# fuelboxmp3.net
KiCad netlist of a schematic drawn in EAGLE
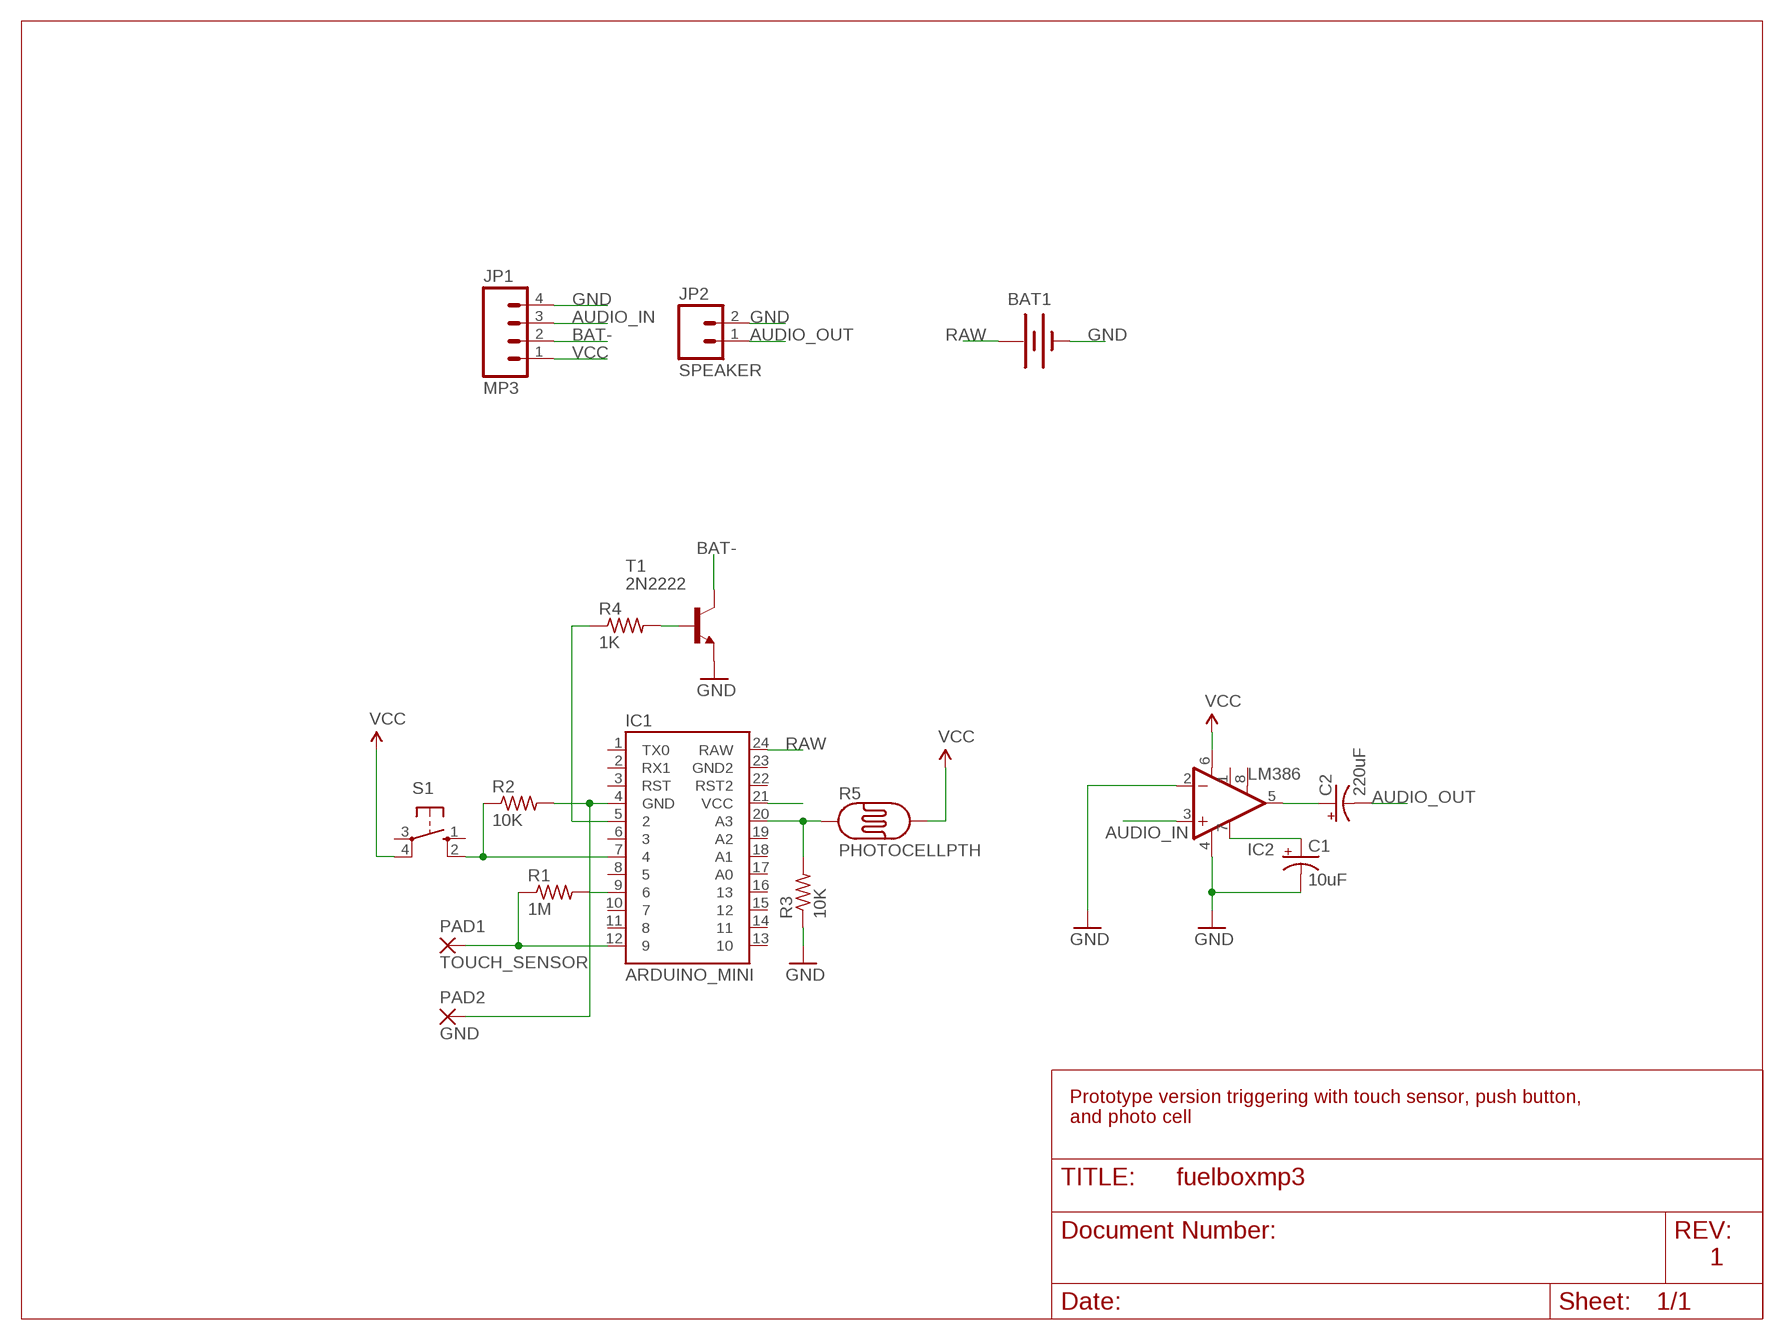
[diagram p0: schematic, sheet 1]

(export (version "E")
  (design (tool "Eeschema 10.0.6"))
  (components
    (comp (ref "BAT1")
      (value "BATTERY1100")
      (footprint "eagle-import:LIPO-1100MAH")
      (libsource (lib "eagle-import") (part "BATTERY1100"))
    )
    (comp (ref "C1")
      (value "10uF")
      (footprint "eagle-import:E2,5-5")
      (libsource (lib "eagle-import") (part "CPOL-USE2.5-5"))
    )
    (comp (ref "C2")
      (value "220uF")
      (footprint "eagle-import:E2,5-6")
      (libsource (lib "eagle-import") (part "CPOL-USE2.5-6"))
    )
    (comp (ref "IC1")
      (value "ARDUINO_MINI")
      (footprint "eagle-import:ARDUINO_MINI")
      (libsource (lib "eagle-import") (part "ARDUINO_MINI"))
    )
    (comp (ref "IC2")
      (value "LM386")
      (footprint "eagle-import:DIP08")
      (libsource (lib "eagle-import") (part "LM386"))
    )
    (comp (ref "JP1")
      (value "MP3")
      (footprint "eagle-import:1X04")
      (libsource (lib "eagle-import") (part "M04PTH"))
    )
    (comp (ref "JP2")
      (value "SPEAKER")
      (footprint "eagle-import:1X02")
      (libsource (lib "eagle-import") (part "M02PTH"))
    )
    (comp (ref "PAD1")
      (value "TOUCH_SENSOR")
      (footprint "eagle-import:3,81_1,1")
      (libsource (lib "eagle-import") (part "WIREPAD3,81/1,1"))
    )
    (comp (ref "PAD2")
      (value "GND")
      (footprint "eagle-import:3,81_1,1")
      (libsource (lib "eagle-import") (part "WIREPAD3,81/1,1"))
    )
    (comp (ref "R1")
      (value "1M")
      (footprint "eagle-import:0204_7")
      (libsource (lib "eagle-import") (part "R-US_0204/7"))
    )
    (comp (ref "R2")
      (value "10K")
      (footprint "eagle-import:0204_7")
      (libsource (lib "eagle-import") (part "R-US_0204/7"))
    )
    (comp (ref "R3")
      (value "10K")
      (footprint "eagle-import:0204_7")
      (libsource (lib "eagle-import") (part "R-US_0204/7"))
    )
    (comp (ref "R4")
      (value "1K")
      (footprint "eagle-import:0204_7")
      (libsource (lib "eagle-import") (part "R-US_0204/7"))
    )
    (comp (ref "R5")
      (value "PHOTOCELLPTH")
      (footprint "eagle-import:PHOTOCELL")
      (libsource (lib "eagle-import") (part "PHOTOCELLPTH"))
    )
    (comp (ref "S1")
      (value "10-XX")
      (footprint "eagle-import:B3F-10XX")
      (fields (field (name "MPN") "B3F-1000"))
      (libsource (lib "eagle-import") (part "10-XX"))
    )
    (comp (ref "T1")
      (value "2N2222")
      (footprint "eagle-import:TO92-EBC-OVAL")
      (libsource (lib "eagle-import") (part "2N2222"))
    )
  )
  (nets
    (net (code "1") (name "/AUDIO_IN") (class "Default")
      (node (ref "IC2") (pin "3") (pinfunction "+IN_3") (pintype "input"))
      (node (ref "JP1") (pin "3") (pinfunction "3_3") (pintype "passive"))
    )
    (net (code "2") (name "/AUDIO_OUT") (class "Default")
      (node (ref "C2") (pin "-") (pinfunction "-_-") (pintype "passive"))
      (node (ref "JP2") (pin "1") (pinfunction "1_1") (pintype "passive"))
    )
    (net (code "3") (name "/BAT-") (class "Default")
      (node (ref "JP1") (pin "2") (pinfunction "2_2") (pintype "passive"))
      (node (ref "T1") (pin "C") (pinfunction "C_C") (pintype "passive"))
    )
    (net (code "4") (name "/RAW") (class "Default")
      (node (ref "BAT1") (pin "+") (pinfunction "+_+") (pintype "power_in"))
      (node (ref "IC1") (pin "24") (pinfunction "RAW_24") (pintype "bidirectional"))
    )
    (net (code "5") (name "GND") (class "Default")
      (node (ref "BAT1") (pin "-") (pinfunction "-_-") (pintype "power_in"))
      (node (ref "C1") (pin "-") (pinfunction "-_-") (pintype "passive"))
      (node (ref "IC1") (pin "4") (pinfunction "GND_4") (pintype "bidirectional"))
      (node (ref "IC2") (pin "2") (pinfunction "-IN_2") (pintype "input"))
      (node (ref "IC2") (pin "4") (pinfunction "V-_4") (pintype "power_in"))
      (node (ref "JP1") (pin "4") (pinfunction "4_4") (pintype "passive"))
      (node (ref "JP2") (pin "2") (pinfunction "2_2") (pintype "passive"))
      (node (ref "PAD2") (pin "1") (pinfunction "P_1") (pintype "passive"))
      (node (ref "R2") (pin "2") (pinfunction "2_2") (pintype "passive"))
      (node (ref "R3") (pin "1") (pinfunction "1_1") (pintype "passive"))
      (node (ref "T1") (pin "E") (pinfunction "E_E") (pintype "passive"))
    )
    (net (code "6") (name "Net-(IC1-2)") (class "Default")
      (node (ref "IC1") (pin "5") (pinfunction "2_5") (pintype "bidirectional"))
      (node (ref "R4") (pin "1") (pinfunction "1_1") (pintype "passive"))
    )
    (net (code "7") (name "Net-(IC1-4)") (class "Default")
      (node (ref "IC1") (pin "7") (pinfunction "4_7") (pintype "bidirectional"))
      (node (ref "R2") (pin "1") (pinfunction "1_1") (pintype "passive"))
      (node (ref "S1") (pin "2") (pinfunction "S1_2") (pintype "passive"))
    )
    (net (code "8") (name "Net-(IC1-6)") (class "Default")
      (node (ref "IC1") (pin "9") (pinfunction "6_9") (pintype "bidirectional"))
      (node (ref "R1") (pin "2") (pinfunction "2_2") (pintype "passive"))
    )
    (net (code "9") (name "Net-(IC1-9)") (class "Default")
      (node (ref "IC1") (pin "12") (pinfunction "9_12") (pintype "bidirectional"))
      (node (ref "PAD1") (pin "1") (pinfunction "P_1") (pintype "passive"))
      (node (ref "R1") (pin "1") (pinfunction "1_1") (pintype "passive"))
    )
    (net (code "10") (name "Net-(IC1-A3)") (class "Default")
      (node (ref "IC1") (pin "20") (pinfunction "A3_20") (pintype "bidirectional"))
      (node (ref "R3") (pin "2") (pinfunction "2_2") (pintype "passive"))
      (node (ref "R5") (pin "1") (pinfunction "P$1_1") (pintype "bidirectional"))
    )
    (net (code "11") (name "Net-(IC2-BP)") (class "Default")
      (node (ref "C1") (pin "+") (pinfunction "+_+") (pintype "passive"))
      (node (ref "IC2") (pin "7") (pinfunction "BP_7") (pintype "bidirectional"))
    )
    (net (code "12") (name "Net-(IC2-OUT)") (class "Default")
      (node (ref "C2") (pin "+") (pinfunction "+_+") (pintype "passive"))
      (node (ref "IC2") (pin "5") (pinfunction "OUT_5") (pintype "output"))
    )
    (net (code "13") (name "Net-(R4-Pad2)") (class "Default")
      (node (ref "R4") (pin "2") (pinfunction "2_2") (pintype "passive"))
      (node (ref "T1") (pin "B") (pinfunction "B_B") (pintype "passive"))
    )
    (net (code "14") (name "VCC") (class "Default")
      (node (ref "IC1") (pin "21") (pinfunction "VCC_21") (pintype "bidirectional"))
      (node (ref "IC2") (pin "6") (pinfunction "V+_6") (pintype "power_in"))
      (node (ref "JP1") (pin "1") (pinfunction "1_1") (pintype "passive"))
      (node (ref "R5") (pin "2") (pinfunction "P$2_2") (pintype "bidirectional"))
      (node (ref "S1") (pin "4") (pinfunction "P1_4") (pintype "passive"))
    )
    (net (code "15") (name "unconnected-(IC1-3-Pad6)") (class "Default")
      (node (ref "IC1") (pin "6") (pinfunction "3_6") (pintype "bidirectional"))
    )
    (net (code "16") (name "unconnected-(IC1-5-Pad8)") (class "Default")
      (node (ref "IC1") (pin "8") (pinfunction "5_8") (pintype "bidirectional"))
    )
    (net (code "17") (name "unconnected-(IC1-7-Pad10)") (class "Default")
      (node (ref "IC1") (pin "10") (pinfunction "7_10") (pintype "bidirectional"))
    )
    (net (code "18") (name "unconnected-(IC1-8-Pad11)") (class "Default")
      (node (ref "IC1") (pin "11") (pinfunction "8_11") (pintype "bidirectional"))
    )
    (net (code "19") (name "unconnected-(IC1-10-Pad13)") (class "Default")
      (node (ref "IC1") (pin "13") (pinfunction "10_13") (pintype "bidirectional"))
    )
    (net (code "20") (name "unconnected-(IC1-11-Pad14)") (class "Default")
      (node (ref "IC1") (pin "14") (pinfunction "11_14") (pintype "bidirectional"))
    )
    (net (code "21") (name "unconnected-(IC1-12-Pad15)") (class "Default")
      (node (ref "IC1") (pin "15") (pinfunction "12_15") (pintype "bidirectional"))
    )
    (net (code "22") (name "unconnected-(IC1-13-Pad16)") (class "Default")
      (node (ref "IC1") (pin "16") (pinfunction "13_16") (pintype "bidirectional"))
    )
    (net (code "23") (name "unconnected-(IC1-A0-Pad17)") (class "Default")
      (node (ref "IC1") (pin "17") (pinfunction "A0_17") (pintype "bidirectional"))
    )
    (net (code "24") (name "unconnected-(IC1-A1-Pad18)") (class "Default")
      (node (ref "IC1") (pin "18") (pinfunction "A1_18") (pintype "bidirectional"))
    )
    (net (code "25") (name "unconnected-(IC1-A2-Pad19)") (class "Default")
      (node (ref "IC1") (pin "19") (pinfunction "A2_19") (pintype "bidirectional"))
    )
    (net (code "26") (name "unconnected-(IC1-GND2-Pad23)") (class "Default")
      (node (ref "IC1") (pin "23") (pinfunction "GND2_23") (pintype "bidirectional"))
    )
    (net (code "27") (name "unconnected-(IC1-RST-Pad3)") (class "Default")
      (node (ref "IC1") (pin "3") (pinfunction "RST_3") (pintype "bidirectional"))
    )
    (net (code "28") (name "unconnected-(IC1-RST2-Pad22)") (class "Default")
      (node (ref "IC1") (pin "22") (pinfunction "RST2_22") (pintype "bidirectional"))
    )
    (net (code "29") (name "unconnected-(IC1-RX1-Pad2)") (class "Default")
      (node (ref "IC1") (pin "2") (pinfunction "RX1_2") (pintype "bidirectional"))
    )
    (net (code "30") (name "unconnected-(IC1-TX0-Pad1)") (class "Default")
      (node (ref "IC1") (pin "1") (pinfunction "TX0_1") (pintype "bidirectional"))
    )
    (net (code "31") (name "unconnected-(IC2-GAIN-Pad1)") (class "Default")
      (node (ref "IC2") (pin "1") (pinfunction "GAIN_1") (pintype "bidirectional"))
    )
    (net (code "32") (name "unconnected-(IC2-GAIN-Pad8)") (class "Default")
      (node (ref "IC2") (pin "8") (pinfunction "GAIN_8") (pintype "bidirectional"))
    )
    (net (code "33") (name "unconnected-(S1-P-Pad3)") (class "Default")
      (node (ref "S1") (pin "3") (pinfunction "P_3") (pintype "passive"))
    )
    (net (code "34") (name "unconnected-(S1-S-Pad1)") (class "Default")
      (node (ref "S1") (pin "1") (pinfunction "S_1") (pintype "passive"))
    )
  )
)
